# LTC3554.net
KiCad netlist of a schematic drawn in Altium Designer
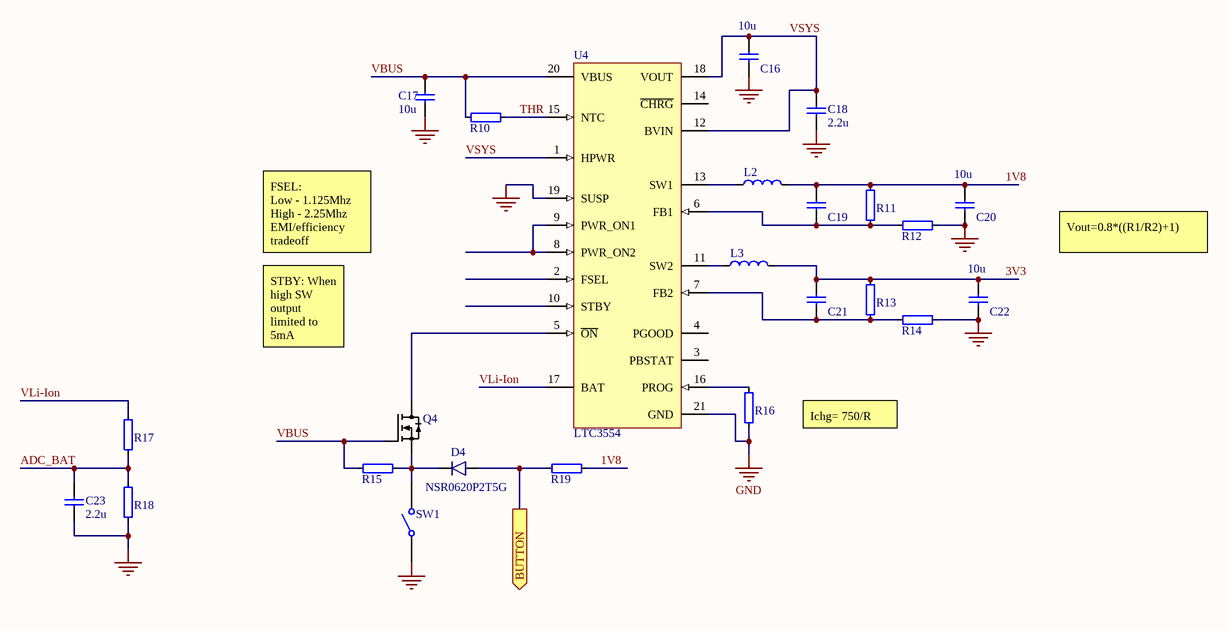
[diagram p0: LTC3554.SchDoc]

(export (version "E")
  (design (tool "Eeschema 10.0.6"))
  (components
    (comp (ref "C16") (value "10u") (footprint "CAPC1608X06L") (libsource (lib "Schlib1") (part "C0603")))
    (comp (ref "C17") (value "10u") (footprint "CAPC1608X06L") (libsource (lib "Schlib1") (part "C0603")))
    (comp (ref "C18") (value "2.2u") (footprint "CAPC1005X04L") (libsource (lib "Schlib1") (part "C0402")))
    (comp (ref "C19") (value "10p") (footprint "CAPC0603X03L_C") (libsource (lib "Schlib1") (part "C0201")))
    (comp (ref "C20") (value "10u") (footprint "CAPC1608X06L") (libsource (lib "Schlib1") (part "C0603")))
    (comp (ref "C21") (value "10p") (footprint "CAPC0603X03L_C") (libsource (lib "Schlib1") (part "C0201")))
    (comp (ref "C22") (value "10u") (footprint "CAPC1608X06L") (libsource (lib "Schlib1") (part "C0603")))
    (comp (ref "C23") (value "2.2u") (footprint "CAPC1005X04L") (libsource (lib "Schlib1") (part "C0402")))
    (comp (ref "D4")
      (value "NSR0620P2T5G")
      (footprint "SODFL100X40-2N")
      (description "20V schottky barrier diode, Vf 350 mV @ 100 mA, Ir 2.0 µA @ 10 V, If 500 mA")
      (fields (field (name "MANUFACTURER") "ON Semiconductor"))
      (libsource (lib "Schlib1") (part "NSR0620P2T5G"))
    )
    (comp (ref "L2")
      (value "LQM21DH100M70L")
      (footprint "FP-LQM21DH_70-MFG")
      (fields (field (name "MANUFACTURER") "Murata"))
      (libsource (lib "Schlib1") (part "LQM21DH100M70L"))
    )
    (comp (ref "L3")
      (value "PE-0805CLH4R7STS")
      (footprint "L0805")
      (description "wire wound chip inductor, 4, 700.00 nh, +/-20%, 25 mHz, RoHS")
      (fields (field (name "MANUFACTURER") "Pulse"))
      (libsource (lib "Schlib1") (part "PE-0805CLH4R7STS"))
    )
    (comp (ref "Q4")
      (value "RV2C010UNT2L")
      (footprint "DFN65P100X40-3L")
      (description "MOSFET Transistor, N Channel, 1 A, 20 V, 0.34 ohm, 4.5 V, 1 V RoHS Compliant: Yes")
      (fields (field (name "MANUFACTURER") "Rohm"))
      (libsource (lib "Schlib1") (part "RV2C010UNT2L"))
    )
    (comp (ref "R10") (value "R0201") (footprint "RESC0603X03L_C") (libsource (lib "Schlib1") (part "R0201")))
    (comp (ref "R11") (value "1.5M") (footprint "RESC0603X03L_C") (libsource (lib "Schlib1") (part "R0201")))
    (comp (ref "R12") (value "1.2M") (footprint "RESC0603X03L_C") (libsource (lib "Schlib1") (part "R0201")))
    (comp (ref "R13") (value "1.5M") (footprint "RESC0603X03L_C") (libsource (lib "Schlib1") (part "R0201")))
    (comp (ref "R14") (value "475k") (footprint "RESC0603X03L_C") (libsource (lib "Schlib1") (part "R0201")))
    (comp (ref "R15") (value "10K") (footprint "RESC0603X03L_C") (libsource (lib "Schlib1") (part "R0201")))
    (comp (ref "R16") (value "1.5k") (footprint "RESC0603X03L_C") (libsource (lib "Schlib1") (part "R0201")))
    (comp (ref "R17") (value "1M") (footprint "RESC0603X03L_C") (libsource (lib "Schlib1") (part "R0201")))
    (comp (ref "R18") (value "510k") (footprint "RESC0603X03L_C") (libsource (lib "Schlib1") (part "R0201")))
    (comp (ref "R19") (value "10K") (footprint "RESC0603X03L_C") (libsource (lib "Schlib1") (part "R0201")))
    (comp (ref "SW1")
      (value "434123050816")
      (footprint "434123050816")
      (description "Switch Tactile Spst-no 0.05A 12V")
      (fields (field (name "MANUFACTURER") "Wurth Electronics"))
      (libsource (lib "Schlib1") (part "434123050816"))
    )
    (comp (ref "U4")
      (value "LTC3554")
      (footprint "LT-UD-20_L")
      (description "IC USB POWER MANAGER 20UTQFN")
      (fields
        (field (name "MANUFACTURER") "Analog Devices / Linear Technology")
        (field (name "MANUFACTURER PART NUMBER") "LTC3554EUD#PBF")
      )
      (libsource (lib "Schlib1") (part "LTC3554EUD#PBF"))
    )
  )
  (nets
    (net (code "1") (name "/1V8") (class "Default")
      (node (ref "C19") (pin "2") (pinfunction "2_2") (pintype "passive"))
      (node (ref "C20") (pin "2") (pinfunction "2_2") (pintype "passive"))
      (node (ref "L2") (pin "2") (pinfunction "2_2") (pintype "passive"))
      (node (ref "R11") (pin "2") (pinfunction "2_2") (pintype "passive"))
      (node (ref "R19") (pin "1") (pinfunction "1_1") (pintype "passive"))
    )
    (net (code "2") (name "/3V3") (class "Default")
      (node (ref "C21") (pin "2") (pinfunction "2_2") (pintype "passive"))
      (node (ref "C22") (pin "2") (pinfunction "2_2") (pintype "passive"))
      (node (ref "L3") (pin "2") (pinfunction "2_2") (pintype "passive"))
      (node (ref "R13") (pin "2") (pinfunction "2_2") (pintype "passive"))
    )
    (net (code "3") (name "/ADC_BAT") (class "Default")
      (node (ref "C23") (pin "2") (pinfunction "2_2") (pintype "passive"))
      (node (ref "R17") (pin "2") (pinfunction "2_2") (pintype "passive"))
      (node (ref "R18") (pin "1") (pinfunction "1_1") (pintype "passive"))
    )
    (net (code "4") (name "/BUTTON") (class "Default")
      (node (ref "D4") (pin "2") (pinfunction "A_2") (pintype "passive"))
      (node (ref "R19") (pin "2") (pinfunction "2_2") (pintype "passive"))
    )
    (net (code "5") (name "/THR") (class "Default")
      (node (ref "R10") (pin "1") (pinfunction "1_1") (pintype "passive"))
      (node (ref "U4") (pin "15") (pinfunction "NTC_15") (pintype "input"))
    )
    (net (code "6") (name "/VBUS") (class "Default")
      (node (ref "C17") (pin "2") (pinfunction "2_2") (pintype "passive"))
      (node (ref "Q4") (pin "1") (pinfunction "G_1") (pintype "passive"))
      (node (ref "R10") (pin "2") (pinfunction "2_2") (pintype "passive"))
      (node (ref "R15") (pin "2") (pinfunction "2_2") (pintype "passive"))
      (node (ref "U4") (pin "20") (pinfunction "VBUS_20") (pintype "power_in"))
    )
    (net (code "7") (name "/VLi-Ion") (class "Default")
      (node (ref "R17") (pin "1") (pinfunction "1_1") (pintype "passive"))
      (node (ref "U4") (pin "17") (pinfunction "BAT_17") (pintype "power_in"))
    )
    (net (code "8") (name "/VSYS") (class "Default")
      (node (ref "C16") (pin "2") (pinfunction "2_2") (pintype "passive"))
      (node (ref "C18") (pin "2") (pinfunction "2_2") (pintype "passive"))
      (node (ref "U4") (pin "1") (pinfunction "HPWR_1") (pintype "input"))
      (node (ref "U4") (pin "12") (pinfunction "BVIN_12") (pintype "power_in"))
      (node (ref "U4") (pin "18") (pinfunction "VOUT_18") (pintype "power_in"))
    )
    (net (code "9") (name "GND") (class "Default")
      (node (ref "C16") (pin "1") (pinfunction "1_1") (pintype "passive"))
      (node (ref "C17") (pin "1") (pinfunction "1_1") (pintype "passive"))
      (node (ref "C18") (pin "1") (pinfunction "1_1") (pintype "passive"))
      (node (ref "C20") (pin "1") (pinfunction "1_1") (pintype "passive"))
      (node (ref "C22") (pin "1") (pinfunction "1_1") (pintype "passive"))
      (node (ref "C23") (pin "1") (pinfunction "1_1") (pintype "passive"))
      (node (ref "R12") (pin "1") (pinfunction "1_1") (pintype "passive"))
      (node (ref "R14") (pin "1") (pinfunction "1_1") (pintype "passive"))
      (node (ref "R16") (pin "1") (pinfunction "1_1") (pintype "passive"))
      (node (ref "R18") (pin "2") (pinfunction "2_2") (pintype "passive"))
      (node (ref "SW1") (pin "1") (pinfunction "1_1") (pintype "passive"))
      (node (ref "U4") (pin "19") (pinfunction "SUSP_19") (pintype "input"))
      (node (ref "U4") (pin "21") (pinfunction "GND_21") (pintype "power_in"))
    )
    (net (code "10") (name "Net-(D4-C)") (class "Default")
      (node (ref "D4") (pin "1") (pinfunction "C_1") (pintype "passive"))
      (node (ref "Q4") (pin "2") (pinfunction "S_2") (pintype "passive"))
      (node (ref "R15") (pin "1") (pinfunction "1_1") (pintype "passive"))
      (node (ref "SW1") (pin "2") (pinfunction "2_2") (pintype "passive"))
    )
    (net (code "11") (name "Net-(Q4-D)") (class "Default")
      (node (ref "Q4") (pin "3") (pinfunction "D_3") (pintype "passive"))
      (node (ref "U4") (pin "5") (pinfunction "~{ON}_5") (pintype "input"))
    )
    (net (code "12") (name "Net-(U4-FB1)") (class "Default")
      (node (ref "C19") (pin "1") (pinfunction "1_1") (pintype "passive"))
      (node (ref "R11") (pin "1") (pinfunction "1_1") (pintype "passive"))
      (node (ref "R12") (pin "2") (pinfunction "2_2") (pintype "passive"))
      (node (ref "U4") (pin "6") (pinfunction "FB1_6") (pintype "input"))
    )
    (net (code "13") (name "Net-(U4-FB2)") (class "Default")
      (node (ref "C21") (pin "1") (pinfunction "1_1") (pintype "passive"))
      (node (ref "R13") (pin "1") (pinfunction "1_1") (pintype "passive"))
      (node (ref "R14") (pin "2") (pinfunction "2_2") (pintype "passive"))
      (node (ref "U4") (pin "7") (pinfunction "FB2_7") (pintype "input"))
    )
    (net (code "14") (name "Net-(U4-PROG)") (class "Default")
      (node (ref "R16") (pin "2") (pinfunction "2_2") (pintype "passive"))
      (node (ref "U4") (pin "16") (pinfunction "PROG_16") (pintype "input"))
    )
    (net (code "15") (name "Net-(U4-PWR_ON1)") (class "Default")
      (node (ref "U4") (pin "8") (pinfunction "PWR_ON2_8") (pintype "input"))
      (node (ref "U4") (pin "9") (pinfunction "PWR_ON1_9") (pintype "input"))
    )
    (net (code "16") (name "Net-(U4-SW1)") (class "Default")
      (node (ref "L2") (pin "1") (pinfunction "1_1") (pintype "passive"))
      (node (ref "U4") (pin "13") (pinfunction "SW1_13") (pintype "power_in"))
    )
    (net (code "17") (name "Net-(U4-SW2)") (class "Default")
      (node (ref "L3") (pin "1") (pinfunction "1_1") (pintype "passive"))
      (node (ref "U4") (pin "11") (pinfunction "SW2_11") (pintype "power_in"))
    )
    (net (code "18") (name "unconnected-(U4-FSEL-Pad2)") (class "Default")
      (node (ref "U4") (pin "2") (pinfunction "FSEL_2") (pintype "input"))
    )
    (net (code "19") (name "unconnected-(U4-PBSTAT-Pad3)") (class "Default")
      (node (ref "U4") (pin "3") (pinfunction "PBSTAT_3") (pintype "tri_state"))
    )
    (net (code "20") (name "unconnected-(U4-PGOOD-Pad4)") (class "Default")
      (node (ref "U4") (pin "4") (pinfunction "PGOOD_4") (pintype "tri_state"))
    )
    (net (code "21") (name "unconnected-(U4-STBY-Pad10)") (class "Default")
      (node (ref "U4") (pin "10") (pinfunction "STBY_10") (pintype "input"))
    )
    (net (code "22") (name "unconnected-(U4-~{CHRG}-Pad14)") (class "Default")
      (node (ref "U4") (pin "14") (pinfunction "~{CHRG}_14") (pintype "tri_state"))
    )
  )
)
